# 7Seg.net
KiCad netlist of a schematic drawn in Altium Designer
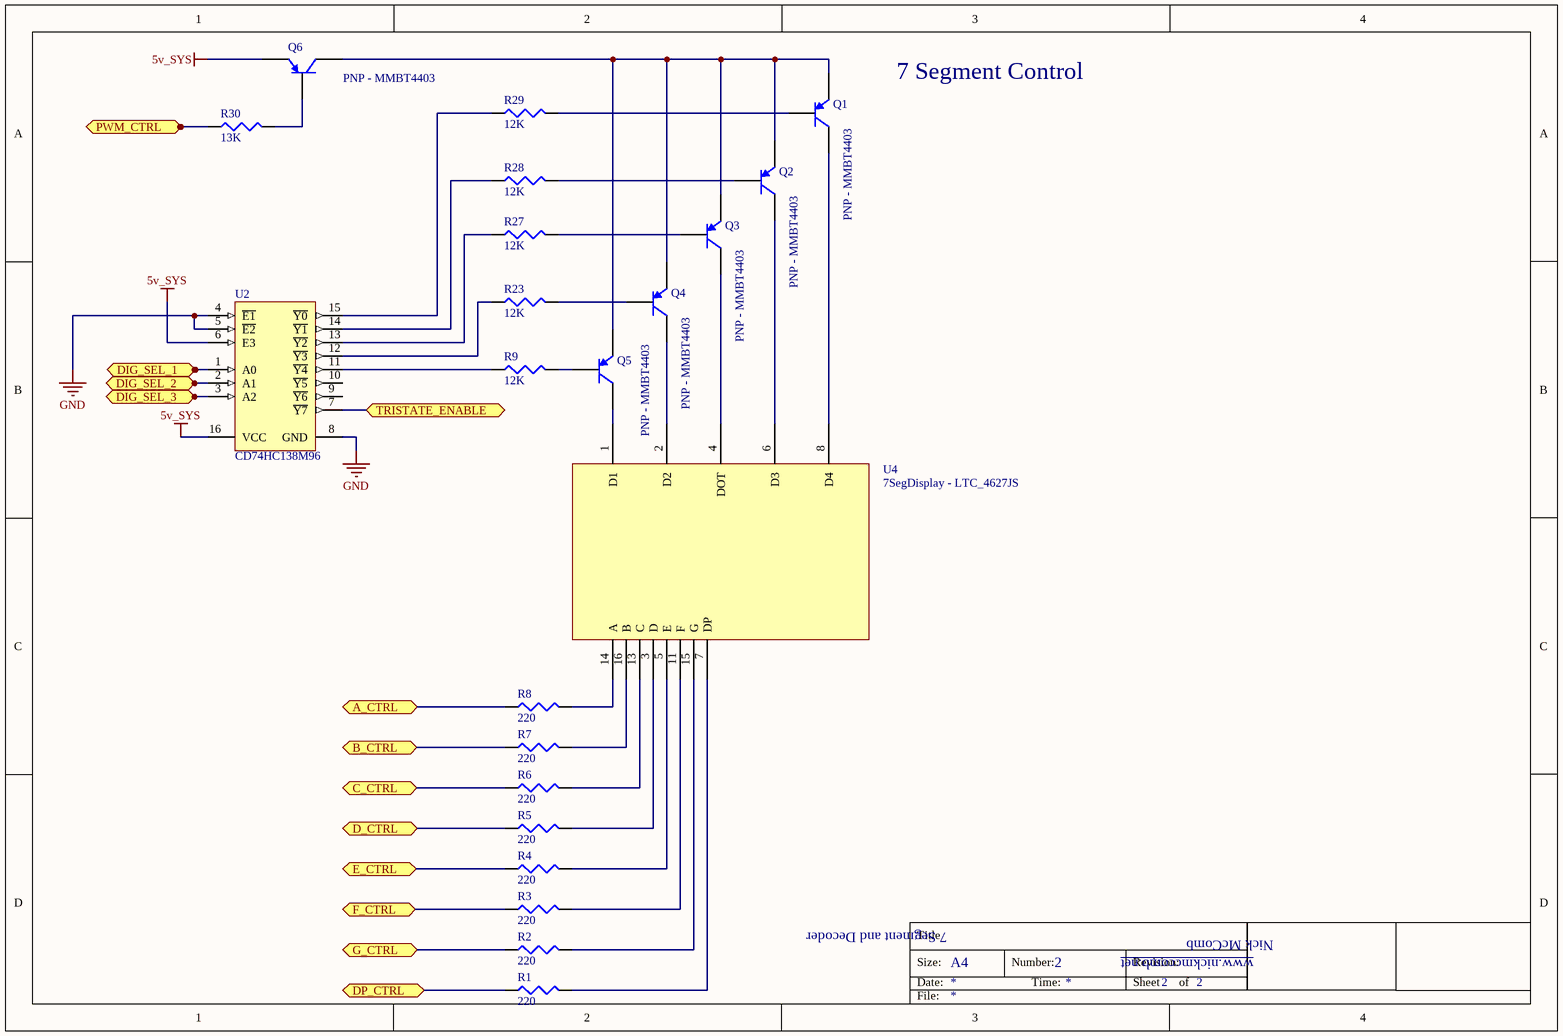
[diagram p0: 7Seg.SchDoc]

(export (version "E")
  (design (tool "Eeschema 10.0.6"))
  (components
    (comp (ref "Q1")
      (value "PNP - MMBT4403")
      (footprint "TO-92A - BJT")
      (description "PNP Bipolar Transistor")
      (libsource (lib "lab2") (part "PNP - MMBT4403"))
    )
    (comp (ref "Q2")
      (value "PNP - MMBT4403")
      (footprint "TO-92A - BJT")
      (description "PNP Bipolar Transistor")
      (libsource (lib "lab2") (part "PNP - MMBT4403"))
    )
    (comp (ref "Q3")
      (value "PNP - MMBT4403")
      (footprint "TO-92A - BJT")
      (description "PNP Bipolar Transistor")
      (libsource (lib "lab2") (part "PNP - MMBT4403"))
    )
    (comp (ref "Q4")
      (value "PNP - MMBT4403")
      (footprint "TO-92A - BJT")
      (description "PNP Bipolar Transistor")
      (libsource (lib "lab2") (part "PNP - MMBT4403"))
    )
    (comp (ref "Q5")
      (value "PNP - MMBT4403")
      (footprint "TO-92A - BJT")
      (description "PNP Bipolar Transistor")
      (libsource (lib "lab2") (part "PNP - MMBT4403"))
    )
    (comp (ref "Q6")
      (value "PNP - MMBT4403")
      (footprint "TO-92A - BJT")
      (description "PNP Bipolar Transistor")
      (libsource (lib "lab2") (part "PNP - MMBT4403"))
    )
    (comp (ref "R1")
      (value "220")
      (footprint "J1-0603")
      (description "Resistor")
      (fields (field (name "PUBLISHER") "Altium Limited"))
      (libsource (lib "lab2") (part "Res3"))
    )
    (comp (ref "R2")
      (value "220")
      (footprint "J1-0603")
      (description "Resistor")
      (fields (field (name "PUBLISHER") "Altium Limited"))
      (libsource (lib "lab2") (part "Res3"))
    )
    (comp (ref "R3")
      (value "220")
      (footprint "J1-0603")
      (description "Resistor")
      (fields (field (name "PUBLISHER") "Altium Limited"))
      (libsource (lib "lab2") (part "Res3"))
    )
    (comp (ref "R4")
      (value "220")
      (footprint "J1-0603")
      (description "Resistor")
      (fields (field (name "PUBLISHER") "Altium Limited"))
      (libsource (lib "lab2") (part "Res3"))
    )
    (comp (ref "R5")
      (value "220")
      (footprint "J1-0603")
      (description "Resistor")
      (fields (field (name "PUBLISHER") "Altium Limited"))
      (libsource (lib "lab2") (part "Res3"))
    )
    (comp (ref "R6")
      (value "220")
      (footprint "J1-0603")
      (description "Resistor")
      (fields (field (name "PUBLISHER") "Altium Limited"))
      (libsource (lib "lab2") (part "Res3"))
    )
    (comp (ref "R7")
      (value "220")
      (footprint "J1-0603")
      (description "Resistor")
      (fields (field (name "PUBLISHER") "Altium Limited"))
      (libsource (lib "lab2") (part "Res3"))
    )
    (comp (ref "R8")
      (value "220")
      (footprint "J1-0603")
      (description "Resistor")
      (fields (field (name "PUBLISHER") "Altium Limited"))
      (libsource (lib "lab2") (part "Res3"))
    )
    (comp (ref "R9")
      (value "12K")
      (footprint "J1-0603")
      (description "Resistor")
      (fields (field (name "PUBLISHER") "Altium Limited"))
      (libsource (lib "lab2") (part "Res3"))
    )
    (comp (ref "R23")
      (value "12K")
      (footprint "J1-0603")
      (description "Resistor")
      (fields (field (name "PUBLISHER") "Altium Limited"))
      (libsource (lib "lab2") (part "Res3"))
    )
    (comp (ref "R27")
      (value "12K")
      (footprint "J1-0603")
      (description "Resistor")
      (fields (field (name "PUBLISHER") "Altium Limited"))
      (libsource (lib "lab2") (part "Res3"))
    )
    (comp (ref "R28")
      (value "12K")
      (footprint "J1-0603")
      (description "Resistor")
      (fields (field (name "PUBLISHER") "Altium Limited"))
      (libsource (lib "lab2") (part "Res3"))
    )
    (comp (ref "R29")
      (value "12K")
      (footprint "J1-0603")
      (description "Resistor")
      (fields (field (name "PUBLISHER") "Altium Limited"))
      (libsource (lib "lab2") (part "Res3"))
    )
    (comp (ref "R30")
      (value "13K")
      (footprint "J1-0603")
      (description "Resistor")
      (fields (field (name "PUBLISHER") "Altium Limited"))
      (libsource (lib "lab2") (part "Res3"))
    )
    (comp (ref "U2")
      (value "CD74HC138M96")
      (footprint "D0016A_L")
      (fields
        (field (name "GENERIC PART NUMBER") "CD74HC138")
        (field (name "MANUFACTURER") "Texas Instruments")
      )
      (libsource (lib "Altium Content Vault") (part "TI-CDX4HCT138-16"))
    )
    (comp (ref "U4") (value "7SegDisplay - LTC_4627JS") (libsource (lib "lab2") (part "7SegDisplay")))
  )
  (nets
    (net (code "1") (name "/A_CTRL") (class "Default")
      (node (ref "R8") (pin "1") (pinfunction "1_1") (pintype "passive"))
    )
    (net (code "2") (name "/B_CTRL") (class "Default")
      (node (ref "R7") (pin "1") (pinfunction "1_1") (pintype "passive"))
    )
    (net (code "3") (name "/C_CTRL") (class "Default")
      (node (ref "R6") (pin "1") (pinfunction "1_1") (pintype "passive"))
    )
    (net (code "4") (name "/DIG_SEL_1") (class "Default")
      (node (ref "U2") (pin "1") (pinfunction "A0_1") (pintype "input"))
    )
    (net (code "5") (name "/DIG_SEL_2") (class "Default")
      (node (ref "U2") (pin "2") (pinfunction "A1_2") (pintype "input"))
    )
    (net (code "6") (name "/DIG_SEL_3") (class "Default")
      (node (ref "U2") (pin "3") (pinfunction "A2_3") (pintype "input"))
    )
    (net (code "7") (name "/DP_CTRL") (class "Default")
      (node (ref "R1") (pin "1") (pinfunction "1_1") (pintype "passive"))
    )
    (net (code "8") (name "/D_CTRL") (class "Default")
      (node (ref "R5") (pin "1") (pinfunction "1_1") (pintype "passive"))
    )
    (net (code "9") (name "/E_CTRL") (class "Default")
      (node (ref "R4") (pin "1") (pinfunction "1_1") (pintype "passive"))
    )
    (net (code "10") (name "/F_CTRL") (class "Default")
      (node (ref "R3") (pin "1") (pinfunction "1_1") (pintype "passive"))
    )
    (net (code "11") (name "/G_CTRL") (class "Default")
      (node (ref "R2") (pin "1") (pinfunction "1_1") (pintype "passive"))
    )
    (net (code "12") (name "/PWM_CTRL") (class "Default")
      (node (ref "R30") (pin "1") (pinfunction "1_1") (pintype "passive"))
    )
    (net (code "13") (name "/TRISTATE_ENABLE") (class "Default")
      (node (ref "U2") (pin "7") (pinfunction "~{Y7}_7") (pintype "output"))
    )
    (net (code "14") (name "5v_SYS") (class "Default")
      (node (ref "Q6") (pin "3") (pinfunction "E_3") (pintype "passive"))
      (node (ref "U2") (pin "16") (pinfunction "VCC_16") (pintype "power_in"))
      (node (ref "U2") (pin "6") (pinfunction "E3_6") (pintype "input"))
    )
    (net (code "15") (name "GND") (class "Default")
      (node (ref "U2") (pin "4") (pinfunction "~{E1}_4") (pintype "input"))
      (node (ref "U2") (pin "5") (pinfunction "~{E2}_5") (pintype "input"))
      (node (ref "U2") (pin "8") (pinfunction "GND_8") (pintype "power_in"))
    )
    (net (code "16") (name "Net-(Q1-B)") (class "Default")
      (node (ref "Q1") (pin "2") (pinfunction "B_2") (pintype "passive"))
      (node (ref "R29") (pin "2") (pinfunction "2_2") (pintype "passive"))
    )
    (net (code "17") (name "Net-(Q1-C)") (class "Default")
      (node (ref "Q1") (pin "1") (pinfunction "C_1") (pintype "passive"))
      (node (ref "U4") (pin "8") (pinfunction "D4_8") (pintype "passive"))
    )
    (net (code "18") (name "Net-(Q1-E)") (class "Default")
      (node (ref "Q1") (pin "3") (pinfunction "E_3") (pintype "passive"))
      (node (ref "Q2") (pin "3") (pinfunction "E_3") (pintype "passive"))
      (node (ref "Q3") (pin "3") (pinfunction "E_3") (pintype "passive"))
      (node (ref "Q4") (pin "3") (pinfunction "E_3") (pintype "passive"))
      (node (ref "Q5") (pin "3") (pinfunction "E_3") (pintype "passive"))
      (node (ref "Q6") (pin "1") (pinfunction "C_1") (pintype "passive"))
    )
    (net (code "19") (name "Net-(Q2-B)") (class "Default")
      (node (ref "Q2") (pin "2") (pinfunction "B_2") (pintype "passive"))
      (node (ref "R28") (pin "2") (pinfunction "2_2") (pintype "passive"))
    )
    (net (code "20") (name "Net-(Q2-C)") (class "Default")
      (node (ref "Q2") (pin "1") (pinfunction "C_1") (pintype "passive"))
      (node (ref "U4") (pin "6") (pinfunction "D3_6") (pintype "passive"))
    )
    (net (code "21") (name "Net-(Q3-B)") (class "Default")
      (node (ref "Q3") (pin "2") (pinfunction "B_2") (pintype "passive"))
      (node (ref "R27") (pin "2") (pinfunction "2_2") (pintype "passive"))
    )
    (net (code "22") (name "Net-(Q3-C)") (class "Default")
      (node (ref "Q3") (pin "1") (pinfunction "C_1") (pintype "passive"))
      (node (ref "U4") (pin "4") (pinfunction "DOT_4") (pintype "passive"))
    )
    (net (code "23") (name "Net-(Q4-B)") (class "Default")
      (node (ref "Q4") (pin "2") (pinfunction "B_2") (pintype "passive"))
      (node (ref "R23") (pin "2") (pinfunction "2_2") (pintype "passive"))
    )
    (net (code "24") (name "Net-(Q4-C)") (class "Default")
      (node (ref "Q4") (pin "1") (pinfunction "C_1") (pintype "passive"))
      (node (ref "U4") (pin "2") (pinfunction "D2_2") (pintype "passive"))
    )
    (net (code "25") (name "Net-(Q5-B)") (class "Default")
      (node (ref "Q5") (pin "2") (pinfunction "B_2") (pintype "passive"))
      (node (ref "R9") (pin "2") (pinfunction "2_2") (pintype "passive"))
    )
    (net (code "26") (name "Net-(Q5-C)") (class "Default")
      (node (ref "Q5") (pin "1") (pinfunction "C_1") (pintype "passive"))
      (node (ref "U4") (pin "1") (pinfunction "D1_1") (pintype "passive"))
    )
    (net (code "27") (name "Net-(Q6-B)") (class "Default")
      (node (ref "Q6") (pin "2") (pinfunction "B_2") (pintype "passive"))
      (node (ref "R30") (pin "2") (pinfunction "2_2") (pintype "passive"))
    )
    (net (code "28") (name "Net-(U2-~{Y0})") (class "Default")
      (node (ref "R29") (pin "1") (pinfunction "1_1") (pintype "passive"))
      (node (ref "U2") (pin "15") (pinfunction "~{Y0}_15") (pintype "output"))
    )
    (net (code "29") (name "Net-(U2-~{Y1})") (class "Default")
      (node (ref "R28") (pin "1") (pinfunction "1_1") (pintype "passive"))
      (node (ref "U2") (pin "14") (pinfunction "~{Y1}_14") (pintype "output"))
    )
    (net (code "30") (name "Net-(U2-~{Y2})") (class "Default")
      (node (ref "R27") (pin "1") (pinfunction "1_1") (pintype "passive"))
      (node (ref "U2") (pin "13") (pinfunction "~{Y2}_13") (pintype "output"))
    )
    (net (code "31") (name "Net-(U2-~{Y3})") (class "Default")
      (node (ref "R23") (pin "1") (pinfunction "1_1") (pintype "passive"))
      (node (ref "U2") (pin "12") (pinfunction "~{Y3}_12") (pintype "output"))
    )
    (net (code "32") (name "Net-(U2-~{Y4})") (class "Default")
      (node (ref "R9") (pin "1") (pinfunction "1_1") (pintype "passive"))
      (node (ref "U2") (pin "11") (pinfunction "~{Y4}_11") (pintype "output"))
    )
    (net (code "33") (name "Net-(U4-A)") (class "Default")
      (node (ref "R8") (pin "2") (pinfunction "2_2") (pintype "passive"))
      (node (ref "U4") (pin "14") (pinfunction "A_14") (pintype "passive"))
    )
    (net (code "34") (name "Net-(U4-B)") (class "Default")
      (node (ref "R7") (pin "2") (pinfunction "2_2") (pintype "passive"))
      (node (ref "U4") (pin "16") (pinfunction "B_16") (pintype "passive"))
    )
    (net (code "35") (name "Net-(U4-C)") (class "Default")
      (node (ref "R6") (pin "2") (pinfunction "2_2") (pintype "passive"))
      (node (ref "U4") (pin "13") (pinfunction "C_13") (pintype "passive"))
    )
    (net (code "36") (name "Net-(U4-D)") (class "Default")
      (node (ref "R5") (pin "2") (pinfunction "2_2") (pintype "passive"))
      (node (ref "U4") (pin "3") (pinfunction "D_3") (pintype "passive"))
    )
    (net (code "37") (name "Net-(U4-DP)") (class "Default")
      (node (ref "R1") (pin "2") (pinfunction "2_2") (pintype "passive"))
      (node (ref "U4") (pin "7") (pinfunction "DP_7") (pintype "passive"))
    )
    (net (code "38") (name "Net-(U4-E)") (class "Default")
      (node (ref "R4") (pin "2") (pinfunction "2_2") (pintype "passive"))
      (node (ref "U4") (pin "5") (pinfunction "E_5") (pintype "passive"))
    )
    (net (code "39") (name "Net-(U4-F)") (class "Default")
      (node (ref "R3") (pin "2") (pinfunction "2_2") (pintype "passive"))
      (node (ref "U4") (pin "11") (pinfunction "F_11") (pintype "passive"))
    )
    (net (code "40") (name "Net-(U4-G)") (class "Default")
      (node (ref "R2") (pin "2") (pinfunction "2_2") (pintype "passive"))
      (node (ref "U4") (pin "15") (pinfunction "G_15") (pintype "passive"))
    )
    (net (code "41") (name "unconnected-(U2-~{Y5}-Pad10)") (class "Default")
      (node (ref "U2") (pin "10") (pinfunction "~{Y5}_10") (pintype "output"))
    )
    (net (code "42") (name "unconnected-(U2-~{Y6}-Pad9)") (class "Default")
      (node (ref "U2") (pin "9") (pinfunction "~{Y6}_9") (pintype "output"))
    )
  )
)
